# DAC.net
KiCad netlist of a schematic drawn in Altium Designer
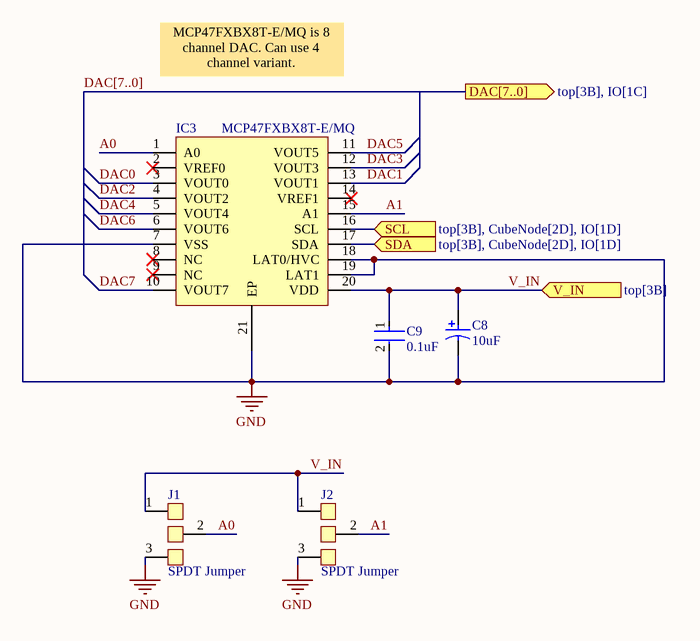
[diagram p0: DAC.SchDoc]

(export (version "E")
  (design (tool "Eeschema 10.0.6"))
  (components
    (comp (ref "C8")
      (value "10uF")
      (footprint "KEMT-A-3216-18-2_M")
      (description "Capacitor, Tantalum, 10 uF, +/- 10%, 10 V, -55 to 125 degC, 2-Pin SMD (1206), RoHS, Tape and Reel")
      (fields (field (name "TOLERANCE") "±10%") (field (name "MANUFACTURER") "Kemet"))
      (libsource (lib "Altium Content Vault") (part "CAP-P-2"))
    )
    (comp (ref "C9")
      (value "0.1uF")
      (footprint "FP-GRM033-0_03-MFG")
      (description "Chip Multilayer Ceramic Capacitors for General Purpose, 0201, 0.10uF, X5R, 15%, 10%, 6.3V")
      (fields (field (name "VOLTAGE") "6.3V") (field (name "TOLERANCE") "10%"))
      (libsource (lib "Altium Content Vault") (part "b4654b650e69147ec39a6b967a45e02"))
    )
    (comp (ref "IC3")
      (value "MCP47FXBX8T-E/MQ")
      (footprint "MCP47FXBX8T-E/MQ")
      (libsource (lib "MCP47FEB04T-EMQ") (part "MCP47FXBX8T-E/MQ"))
    )
    (comp (ref "J1")
      (value "SPDT Jumper")
      (footprint "SPDT Jumper")
      (libsource (lib "jumpers") (part "SPDT Jumper"))
    )
    (comp (ref "J2")
      (value "SPDT Jumper")
      (footprint "SPDT Jumper")
      (libsource (lib "jumpers") (part "SPDT Jumper"))
    )
  )
  (nets
    (net (code "1") (name "/A0") (class "Default")
      (node (ref "IC3") (pin "1") (pinfunction "A0_1") (pintype "passive"))
      (node (ref "J1") (pin "2") (pinfunction "2_2") (pintype "passive"))
    )
    (net (code "2") (name "/A1") (class "Default")
      (node (ref "IC3") (pin "15") (pinfunction "A1_15") (pintype "passive"))
      (node (ref "J2") (pin "2") (pinfunction "2_2") (pintype "passive"))
    )
    (net (code "3") (name "/DAC0") (class "Default")
      (node (ref "IC3") (pin "3") (pinfunction "VOUT0_3") (pintype "passive"))
    )
    (net (code "4") (name "/DAC1") (class "Default")
      (node (ref "IC3") (pin "13") (pinfunction "VOUT1_13") (pintype "passive"))
    )
    (net (code "5") (name "/DAC2") (class "Default")
      (node (ref "IC3") (pin "4") (pinfunction "VOUT2_4") (pintype "passive"))
    )
    (net (code "6") (name "/DAC3") (class "Default")
      (node (ref "IC3") (pin "12") (pinfunction "VOUT3_12") (pintype "passive"))
    )
    (net (code "7") (name "/DAC4") (class "Default")
      (node (ref "IC3") (pin "5") (pinfunction "VOUT4_5") (pintype "passive"))
    )
    (net (code "8") (name "/DAC5") (class "Default")
      (node (ref "IC3") (pin "11") (pinfunction "VOUT5_11") (pintype "passive"))
    )
    (net (code "9") (name "/DAC6") (class "Default")
      (node (ref "IC3") (pin "6") (pinfunction "VOUT6_6") (pintype "passive"))
    )
    (net (code "10") (name "/DAC7") (class "Default")
      (node (ref "IC3") (pin "10") (pinfunction "VOUT7_10") (pintype "passive"))
    )
    (net (code "12") (name "/SCL") (class "Default")
      (node (ref "IC3") (pin "16") (pinfunction "SCL_16") (pintype "passive"))
    )
    (net (code "13") (name "/SDA") (class "Default")
      (node (ref "IC3") (pin "17") (pinfunction "SDA_17") (pintype "passive"))
    )
    (net (code "14") (name "/V_IN") (class "Default")
      (node (ref "C8") (pin "1") (pinfunction "1_1") (pintype "passive"))
      (node (ref "C9") (pin "1") (pinfunction "1_1") (pintype "passive"))
      (node (ref "IC3") (pin "20") (pinfunction "VDD_20") (pintype "passive"))
      (node (ref "J1") (pin "1") (pinfunction "1_1") (pintype "passive"))
      (node (ref "J2") (pin "1") (pinfunction "1_1") (pintype "passive"))
    )
    (net (code "15") (name "GND") (class "Default")
      (node (ref "C8") (pin "2") (pinfunction "2_2") (pintype "passive"))
      (node (ref "C9") (pin "2") (pinfunction "2_2") (pintype "passive"))
      (node (ref "IC3") (pin "18") (pinfunction "LAT0/HVC_18") (pintype "passive"))
      (node (ref "IC3") (pin "19") (pinfunction "LAT1_19") (pintype "passive"))
      (node (ref "IC3") (pin "21") (pinfunction "EP_21") (pintype "passive"))
      (node (ref "IC3") (pin "7") (pinfunction "VSS_7") (pintype "passive"))
      (node (ref "J1") (pin "3") (pinfunction "3_3") (pintype "passive"))
      (node (ref "J2") (pin "3") (pinfunction "3_3") (pintype "passive"))
    )
    (net (code "16") (name "unconnected-(IC3-NC-Pad8)") (class "Default")
      (node (ref "IC3") (pin "8") (pinfunction "NC_8") (pintype "passive+no_connect"))
    )
    (net (code "17") (name "unconnected-(IC3-NC-Pad9)") (class "Default")
      (node (ref "IC3") (pin "9") (pinfunction "NC_9") (pintype "passive+no_connect"))
    )
    (net (code "18") (name "unconnected-(IC3-VREF0-Pad2)") (class "Default")
      (node (ref "IC3") (pin "2") (pinfunction "VREF0_2") (pintype "passive+no_connect"))
    )
    (net (code "19") (name "unconnected-(IC3-VREF1-Pad14)") (class "Default")
      (node (ref "IC3") (pin "14") (pinfunction "VREF1_14") (pintype "passive+no_connect"))
    )
  )
)
